# wifi-board.net
KiCad netlist of a schematic drawn in EAGLE
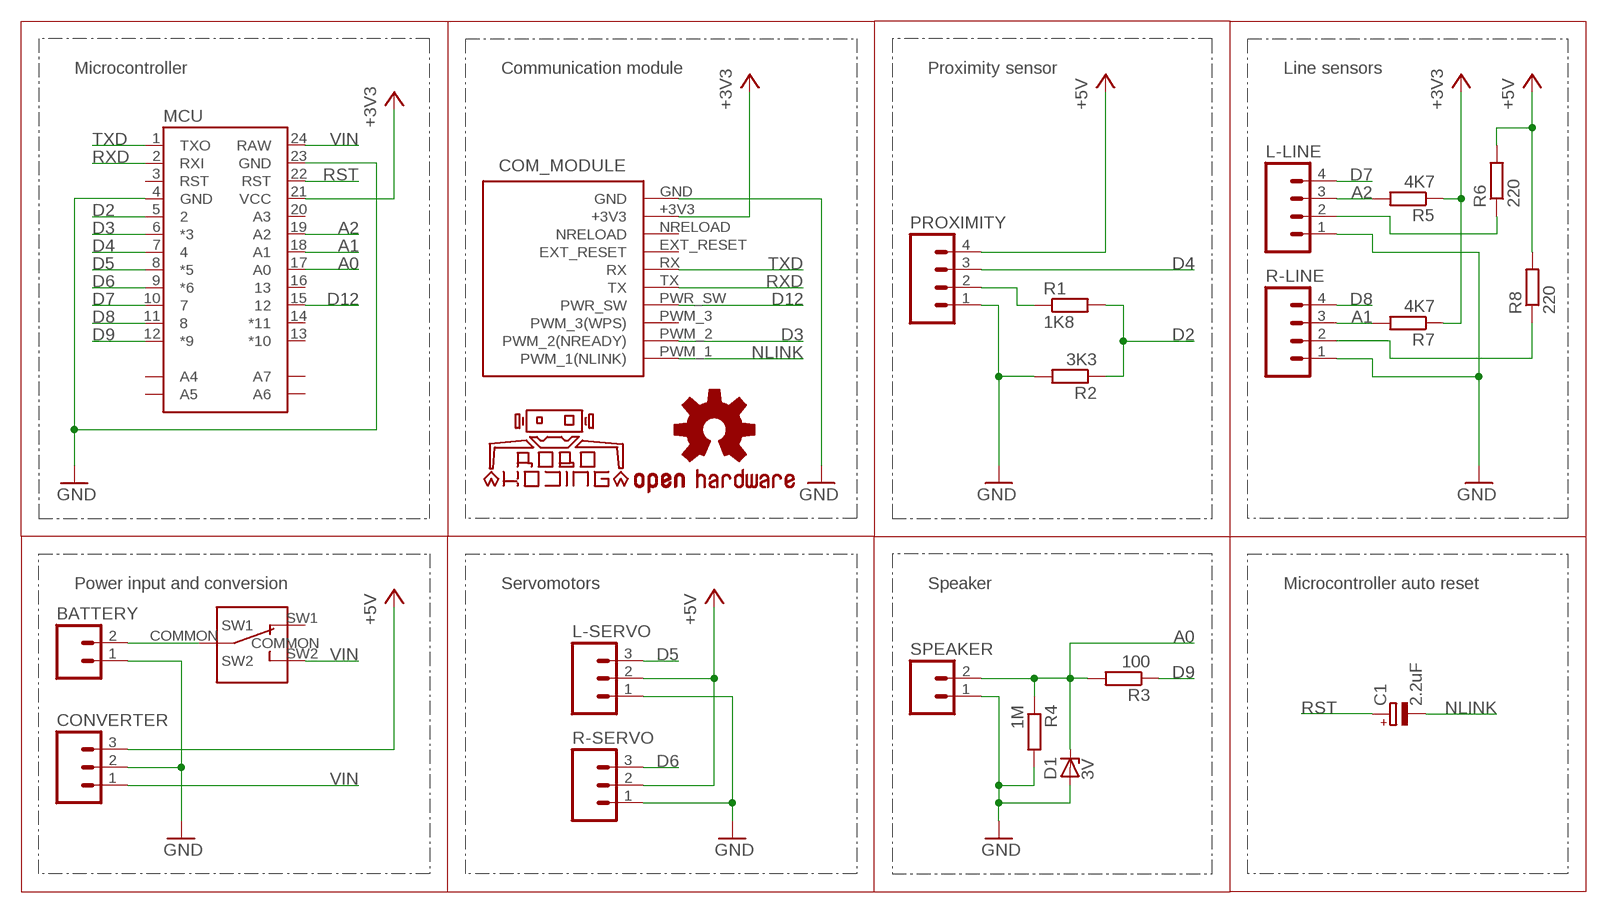
[diagram p0: schematic, sheet 1]

(export (version "E")
  (design (tool "Eeschema 10.0.6"))
  (components
    (comp (ref "BATTERY")
      (value "M02LOCK_LONGPADS")
      (footprint "eagle-import:1X02_LOCK_LONGPADS")
      (libsource (lib "eagle-import") (part "M02LOCK_LONGPADS"))
    )
    (comp (ref "C1")
      (value "2.2uF")
      (footprint "eagle-import:E2-5")
      (libsource (lib "eagle-import") (part "CPOL-EUE2-5"))
    )
    (comp (ref "COM_MODULE")
      (value "USR_WIFI-T")
      (footprint "eagle-import:WIFI_MODULE-T")
      (libsource (lib "eagle-import") (part "USR_WIFI-T"))
    )
    (comp (ref "CONVERTER")
      (value "M03LOCK_LONGPADS")
      (footprint "eagle-import:1X03_LOCK_LONGPADS")
      (libsource (lib "eagle-import") (part "M03LOCK_LONGPADS"))
    )
    (comp (ref "D1")
      (value "3V")
      (footprint "eagle-import:DO35Z10")
      (libsource (lib "eagle-import") (part "1N821"))
    )
    (comp (ref "L-LINE")
      (value "M04LOCK_LONGPADS")
      (footprint "eagle-import:1X04_LOCK_LONGPADS")
      (libsource (lib "eagle-import") (part "M04LOCK_LONGPADS"))
    )
    (comp (ref "L-SERVO")
      (value "M03LOCK_LONGPADS")
      (footprint "eagle-import:1X03_LOCK_LONGPADS")
      (libsource (lib "eagle-import") (part "M03LOCK_LONGPADS"))
    )
    (comp (ref "LOGO1")
      (value "OSHW-LOGOM")
      (footprint "eagle-import:OSHW-LOGO-M")
      (libsource (lib "eagle-import") (part "OSHW-LOGOM"))
    )
    (comp (ref "LOGO2")
      (value "ROBOKODING-LOGOM")
      (footprint "eagle-import:ROBOKODING-LOGO-M")
      (libsource (lib "eagle-import") (part "ROBOKODING-LOGOM"))
    )
    (comp (ref "MCU")
      (value "ARDUINO_PRO_MINI")
      (footprint "eagle-import:ARDUINO_PRO_MINI")
      (libsource (lib "eagle-import") (part "ARDUINO_PRO_MINI"))
    )
    (comp (ref "POWER")
      (value "SPDT_SLIDE_SWITCH")
      (footprint "eagle-import:SPDT_SLIDE_SWITCH")
      (libsource (lib "eagle-import") (part "SPDT_SLIDE_SWITCH"))
    )
    (comp (ref "PROXIMITY")
      (value "M04LOCK_LONGPADS")
      (footprint "eagle-import:1X04_LOCK_LONGPADS")
      (libsource (lib "eagle-import") (part "M04LOCK_LONGPADS"))
    )
    (comp (ref "R-LINE")
      (value "M04LOCK_LONGPADS")
      (footprint "eagle-import:1X04_LOCK_LONGPADS")
      (libsource (lib "eagle-import") (part "M04LOCK_LONGPADS"))
    )
    (comp (ref "R-SERVO")
      (value "M03LOCK_LONGPADS")
      (footprint "eagle-import:1X03_LOCK_LONGPADS")
      (libsource (lib "eagle-import") (part "M03LOCK_LONGPADS"))
    )
    (comp (ref "R1")
      (value "1K8")
      (footprint "eagle-import:0204_5")
      (libsource (lib "eagle-import") (part "R-EU_0204/5"))
    )
    (comp (ref "R2")
      (value "3K3")
      (footprint "eagle-import:0204_5")
      (libsource (lib "eagle-import") (part "R-EU_0204/5"))
    )
    (comp (ref "R3")
      (value "100")
      (footprint "eagle-import:0204_5")
      (libsource (lib "eagle-import") (part "R-EU_0204/5"))
    )
    (comp (ref "R4")
      (value "1M")
      (footprint "eagle-import:0204_5")
      (libsource (lib "eagle-import") (part "R-EU_0204/5"))
    )
    (comp (ref "R5")
      (value "4K7")
      (footprint "eagle-import:0204_5")
      (libsource (lib "eagle-import") (part "R-EU_0204/5"))
    )
    (comp (ref "R6")
      (value "220")
      (footprint "eagle-import:0204_5")
      (libsource (lib "eagle-import") (part "R-EU_0204/5"))
    )
    (comp (ref "R7")
      (value "4K7")
      (footprint "eagle-import:0204_5")
      (libsource (lib "eagle-import") (part "R-EU_0204/5"))
    )
    (comp (ref "R8")
      (value "220")
      (footprint "eagle-import:0204_5")
      (libsource (lib "eagle-import") (part "R-EU_0204/5"))
    )
    (comp (ref "SPEAKER")
      (value "M02LOCK_LONGPADS")
      (footprint "eagle-import:1X02_LOCK_LONGPADS")
      (libsource (lib "eagle-import") (part "M02LOCK_LONGPADS"))
    )
  )
  (nets
    (net (code "1") (name "+3V3") (class "Default")
      (node (ref "COM_MODULE") (pin "+3V3") (pinfunction "+3V3_+3V3") (pintype "power_in"))
      (node (ref "MCU") (pin "21") (pinfunction "VCC_21") (pintype "bidirectional"))
      (node (ref "R5") (pin "1") (pinfunction "1_1") (pintype "passive"))
      (node (ref "R7") (pin "1") (pinfunction "1_1") (pintype "passive"))
    )
    (net (code "2") (name "+5V") (class "Default")
      (node (ref "CONVERTER") (pin "3") (pinfunction "3_3") (pintype "passive"))
      (node (ref "L-SERVO") (pin "2") (pinfunction "2_2") (pintype "passive"))
      (node (ref "PROXIMITY") (pin "4") (pinfunction "4_4") (pintype "passive"))
      (node (ref "R-SERVO") (pin "2") (pinfunction "2_2") (pintype "passive"))
      (node (ref "R6") (pin "2") (pinfunction "2_2") (pintype "passive"))
      (node (ref "R8") (pin "2") (pinfunction "2_2") (pintype "passive"))
    )
    (net (code "3") (name "/A0") (class "Default")
      (node (ref "D1") (pin "C") (pinfunction "C_C") (pintype "passive"))
      (node (ref "MCU") (pin "17") (pinfunction "A0_17") (pintype "bidirectional"))
      (node (ref "R3") (pin "2") (pinfunction "2_2") (pintype "passive"))
      (node (ref "R4") (pin "1") (pinfunction "1_1") (pintype "passive"))
      (node (ref "SPEAKER") (pin "2") (pinfunction "2_2") (pintype "passive"))
    )
    (net (code "4") (name "/A1") (class "Default")
      (node (ref "MCU") (pin "18") (pinfunction "A1_18") (pintype "bidirectional"))
      (node (ref "R-LINE") (pin "3") (pinfunction "3_3") (pintype "passive"))
      (node (ref "R7") (pin "2") (pinfunction "2_2") (pintype "passive"))
    )
    (net (code "5") (name "/A2") (class "Default")
      (node (ref "L-LINE") (pin "3") (pinfunction "3_3") (pintype "passive"))
      (node (ref "MCU") (pin "19") (pinfunction "A2_19") (pintype "bidirectional"))
      (node (ref "R5") (pin "2") (pinfunction "2_2") (pintype "passive"))
    )
    (net (code "6") (name "/D2") (class "Default")
      (node (ref "MCU") (pin "5") (pinfunction "2_5") (pintype "bidirectional"))
      (node (ref "R1") (pin "2") (pinfunction "2_2") (pintype "passive"))
      (node (ref "R2") (pin "1") (pinfunction "1_1") (pintype "passive"))
    )
    (net (code "7") (name "/D3") (class "Default")
      (node (ref "COM_MODULE") (pin "PWM_2") (pinfunction "PWM_2(NREADY)_PWM_2") (pintype "bidirectional"))
      (node (ref "MCU") (pin "6") (pinfunction "*3_6") (pintype "bidirectional"))
    )
    (net (code "8") (name "/D4") (class "Default")
      (node (ref "MCU") (pin "7") (pinfunction "4_7") (pintype "bidirectional"))
      (node (ref "PROXIMITY") (pin "3") (pinfunction "3_3") (pintype "passive"))
    )
    (net (code "9") (name "/D5") (class "Default")
      (node (ref "L-SERVO") (pin "3") (pinfunction "3_3") (pintype "passive"))
      (node (ref "MCU") (pin "8") (pinfunction "*5_8") (pintype "bidirectional"))
    )
    (net (code "10") (name "/D6") (class "Default")
      (node (ref "MCU") (pin "9") (pinfunction "*6_9") (pintype "bidirectional"))
      (node (ref "R-SERVO") (pin "3") (pinfunction "3_3") (pintype "passive"))
    )
    (net (code "11") (name "/D7") (class "Default")
      (node (ref "L-LINE") (pin "4") (pinfunction "4_4") (pintype "passive"))
      (node (ref "MCU") (pin "10") (pinfunction "7_10") (pintype "bidirectional"))
    )
    (net (code "12") (name "/D8") (class "Default")
      (node (ref "MCU") (pin "11") (pinfunction "8_11") (pintype "bidirectional"))
      (node (ref "R-LINE") (pin "4") (pinfunction "4_4") (pintype "passive"))
    )
    (net (code "13") (name "/D9") (class "Default")
      (node (ref "MCU") (pin "12") (pinfunction "*9_12") (pintype "bidirectional"))
      (node (ref "R3") (pin "1") (pinfunction "1_1") (pintype "passive"))
    )
    (net (code "14") (name "/D12") (class "Default")
      (node (ref "COM_MODULE") (pin "PWR_SW") (pinfunction "PWR_SW_PWR_SW") (pintype "bidirectional"))
      (node (ref "MCU") (pin "15") (pinfunction "12_15") (pintype "bidirectional"))
    )
    (net (code "15") (name "/NLINK") (class "Default")
      (node (ref "C1") (pin "-") (pinfunction "-_-") (pintype "passive"))
      (node (ref "COM_MODULE") (pin "PWM_1") (pinfunction "PWM_1(NLINK)_PWM_1") (pintype "bidirectional"))
    )
    (net (code "16") (name "/RST") (class "Default")
      (node (ref "C1") (pin "+") (pinfunction "+_+") (pintype "passive"))
      (node (ref "MCU") (pin "22") (pinfunction "RST_22") (pintype "bidirectional"))
    )
    (net (code "17") (name "/RXD") (class "Default")
      (node (ref "COM_MODULE") (pin "TX") (pinfunction "TX_TX") (pintype "bidirectional"))
      (node (ref "MCU") (pin "2") (pinfunction "RXI_2") (pintype "bidirectional"))
    )
    (net (code "18") (name "/TXD") (class "Default")
      (node (ref "COM_MODULE") (pin "RX") (pinfunction "RX_RX") (pintype "bidirectional"))
      (node (ref "MCU") (pin "1") (pinfunction "TXO_1") (pintype "bidirectional"))
    )
    (net (code "19") (name "/VIN") (class "Default")
      (node (ref "CONVERTER") (pin "1") (pinfunction "1_1") (pintype "passive"))
      (node (ref "MCU") (pin "24") (pinfunction "RAW_24") (pintype "bidirectional"))
      (node (ref "POWER") (pin "SW2") (pinfunction "SW2_SW2") (pintype "bidirectional"))
    )
    (net (code "20") (name "GND") (class "Default")
      (node (ref "BATTERY") (pin "1") (pinfunction "1_1") (pintype "passive"))
      (node (ref "COM_MODULE") (pin "GND") (pinfunction "GND_GND") (pintype "power_in"))
      (node (ref "CONVERTER") (pin "2") (pinfunction "2_2") (pintype "passive"))
      (node (ref "D1") (pin "A") (pinfunction "A_A") (pintype "passive"))
      (node (ref "L-LINE") (pin "1") (pinfunction "1_1") (pintype "passive"))
      (node (ref "L-SERVO") (pin "1") (pinfunction "1_1") (pintype "passive"))
      (node (ref "MCU") (pin "23") (pinfunction "GND_23") (pintype "bidirectional"))
      (node (ref "MCU") (pin "4") (pinfunction "GND_4") (pintype "bidirectional"))
      (node (ref "PROXIMITY") (pin "1") (pinfunction "1_1") (pintype "passive"))
      (node (ref "R-LINE") (pin "1") (pinfunction "1_1") (pintype "passive"))
      (node (ref "R-SERVO") (pin "1") (pinfunction "1_1") (pintype "passive"))
      (node (ref "R2") (pin "2") (pinfunction "2_2") (pintype "passive"))
      (node (ref "R4") (pin "2") (pinfunction "2_2") (pintype "passive"))
      (node (ref "SPEAKER") (pin "1") (pinfunction "1_1") (pintype "passive"))
    )
    (net (code "21") (name "Net-(BATTERY-Pad2)") (class "Default")
      (node (ref "BATTERY") (pin "2") (pinfunction "2_2") (pintype "passive"))
      (node (ref "POWER") (pin "COMMON") (pinfunction "COMMON_COMMON") (pintype "bidirectional"))
    )
    (net (code "22") (name "Net-(L-LINE-Pad2)") (class "Default")
      (node (ref "L-LINE") (pin "2") (pinfunction "2_2") (pintype "passive"))
      (node (ref "R6") (pin "1") (pinfunction "1_1") (pintype "passive"))
    )
    (net (code "23") (name "Net-(PROXIMITY-Pad2)") (class "Default")
      (node (ref "PROXIMITY") (pin "2") (pinfunction "2_2") (pintype "passive"))
      (node (ref "R1") (pin "1") (pinfunction "1_1") (pintype "passive"))
    )
    (net (code "24") (name "Net-(R-LINE-Pad2)") (class "Default")
      (node (ref "R-LINE") (pin "2") (pinfunction "2_2") (pintype "passive"))
      (node (ref "R8") (pin "1") (pinfunction "1_1") (pintype "passive"))
    )
    (net (code "25") (name "unconnected-(COM_MODULE-PWM_3(WPS)-PadPWM_3)") (class "Default")
      (node (ref "COM_MODULE") (pin "PWM_3") (pinfunction "PWM_3(WPS)_PWM_3") (pintype "bidirectional"))
    )
    (net (code "26") (name "unconnected-(COM_MODULE-PadEXT_RESET)") (class "Default")
      (node (ref "COM_MODULE") (pin "EXT_RESET") (pinfunction "EXT_RESET_EXT_RESET") (pintype "bidirectional"))
    )
    (net (code "27") (name "unconnected-(COM_MODULE-PadNRELOAD)") (class "Default")
      (node (ref "COM_MODULE") (pin "NRELOAD") (pinfunction "NRELOAD_NRELOAD") (pintype "bidirectional"))
    )
    (net (code "28") (name "unconnected-(MCU-*10-Pad13)") (class "Default")
      (node (ref "MCU") (pin "13") (pinfunction "*10_13") (pintype "bidirectional"))
    )
    (net (code "29") (name "unconnected-(MCU-*11-Pad14)") (class "Default")
      (node (ref "MCU") (pin "14") (pinfunction "*11_14") (pintype "bidirectional"))
    )
    (net (code "30") (name "unconnected-(MCU-13-Pad16)") (class "Default")
      (node (ref "MCU") (pin "16") (pinfunction "13_16") (pintype "bidirectional"))
    )
    (net (code "31") (name "unconnected-(MCU-A3-Pad20)") (class "Default")
      (node (ref "MCU") (pin "20") (pinfunction "A3_20") (pintype "bidirectional"))
    )
    (net (code "32") (name "unconnected-(MCU-RST-Pad3)") (class "Default")
      (node (ref "MCU") (pin "3") (pinfunction "RST_3") (pintype "bidirectional"))
    )
    (net (code "33") (name "unconnected-(POWER-PadSW1)") (class "Default")
      (node (ref "POWER") (pin "SW1") (pinfunction "SW1_SW1") (pintype "bidirectional"))
    )
  )
)
